# busadapt.net
KiCad netlist of a schematic drawn in EAGLE
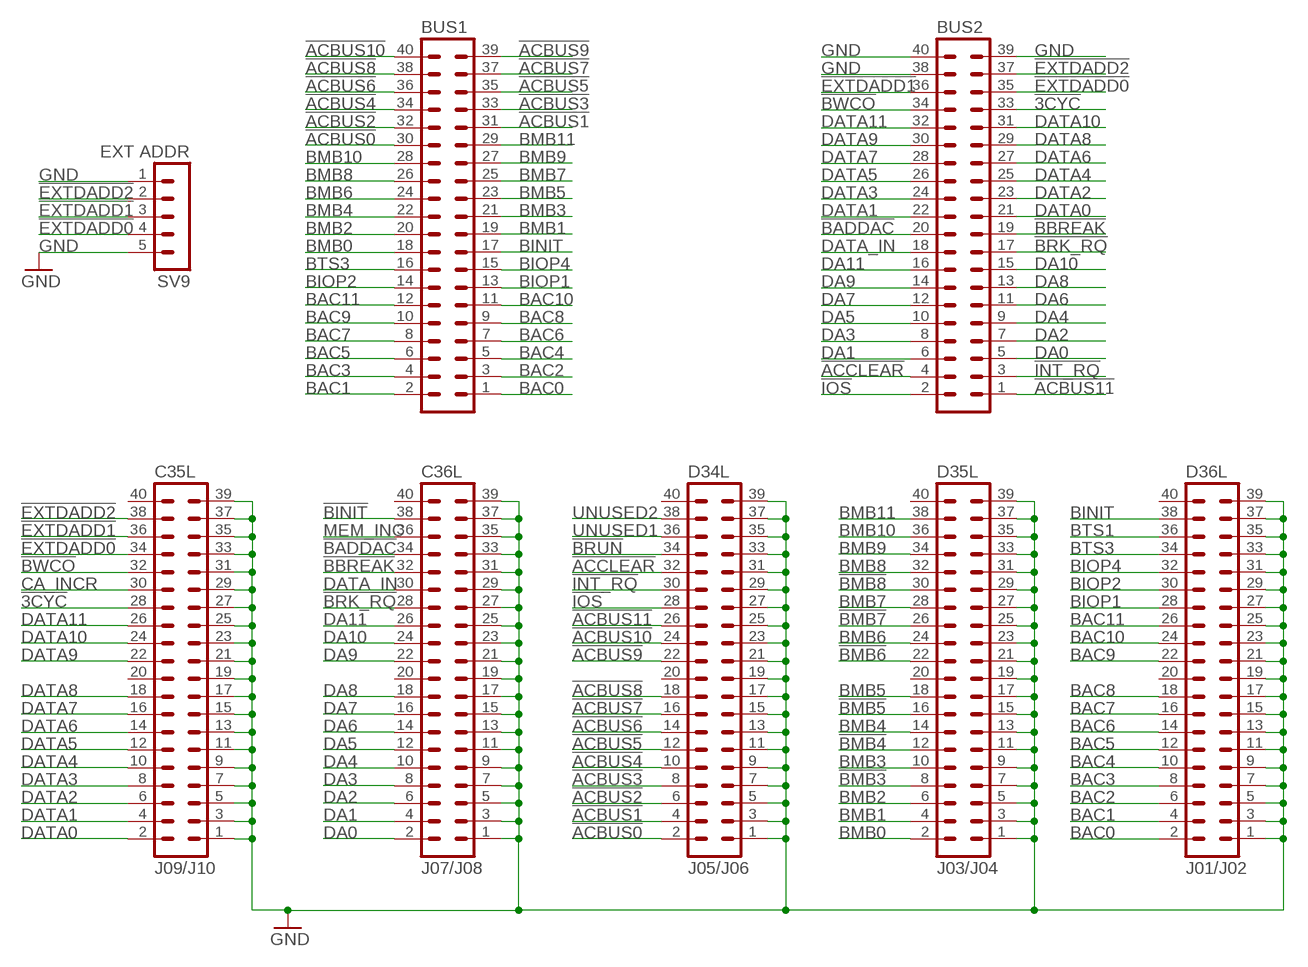
[diagram p0: schematic, sheet 1]

(export (version "E")
  (design (tool "Eeschema 10.0.6"))
  (components
    (comp (ref "BUS1")
      (value "MA20-2")
      (footprint "eagle-import:MA20-2")
      (libsource (lib "eagle-import") (part "MA20-2"))
    )
    (comp (ref "BUS2")
      (value "MA20-2")
      (footprint "eagle-import:MA20-2")
      (libsource (lib "eagle-import") (part "MA20-2"))
    )
    (comp (ref "C35L")
      (value "J09/J10")
      (footprint "eagle-import:MA20-2")
      (libsource (lib "eagle-import") (part "MA20-2"))
    )
    (comp (ref "C36L")
      (value "J07/J08")
      (footprint "eagle-import:MA20-2")
      (libsource (lib "eagle-import") (part "MA20-2"))
    )
    (comp (ref "D34L")
      (value "J05/J06")
      (footprint "eagle-import:MA20-2")
      (libsource (lib "eagle-import") (part "MA20-2"))
    )
    (comp (ref "D35L")
      (value "J03/J04")
      (footprint "eagle-import:MA20-2")
      (libsource (lib "eagle-import") (part "MA20-2"))
    )
    (comp (ref "D36L")
      (value "J01/J02")
      (footprint "eagle-import:MA20-2")
      (libsource (lib "eagle-import") (part "MA20-2"))
    )
    (comp (ref "SV9")
      (value "EXT ADDR")
      (footprint "eagle-import:MA05-1")
      (libsource (lib "eagle-import") (part "MA05-1"))
    )
  )
  (nets
    (net (code "1") (name "/BAC0") (class "Default")
      (node (ref "BUS1") (pin "1") (pinfunction "1_1") (pintype "passive"))
      (node (ref "D36L") (pin "2") (pinfunction "2_2") (pintype "passive"))
    )
    (net (code "2") (name "/BAC1") (class "Default")
      (node (ref "BUS1") (pin "2") (pinfunction "2_2") (pintype "passive"))
      (node (ref "D36L") (pin "4") (pinfunction "4_4") (pintype "passive"))
    )
    (net (code "3") (name "/BAC2") (class "Default")
      (node (ref "BUS1") (pin "3") (pinfunction "3_3") (pintype "passive"))
      (node (ref "D36L") (pin "6") (pinfunction "6_6") (pintype "passive"))
    )
    (net (code "4") (name "/BAC3") (class "Default")
      (node (ref "BUS1") (pin "4") (pinfunction "4_4") (pintype "passive"))
      (node (ref "D36L") (pin "8") (pinfunction "8_8") (pintype "passive"))
    )
    (net (code "5") (name "/BAC4") (class "Default")
      (node (ref "BUS1") (pin "5") (pinfunction "5_5") (pintype "passive"))
      (node (ref "D36L") (pin "10") (pinfunction "10_10") (pintype "passive"))
    )
    (net (code "6") (name "/BAC5") (class "Default")
      (node (ref "BUS1") (pin "6") (pinfunction "6_6") (pintype "passive"))
      (node (ref "D36L") (pin "12") (pinfunction "12_12") (pintype "passive"))
    )
    (net (code "7") (name "/BAC6") (class "Default")
      (node (ref "BUS1") (pin "7") (pinfunction "7_7") (pintype "passive"))
      (node (ref "D36L") (pin "14") (pinfunction "14_14") (pintype "passive"))
    )
    (net (code "8") (name "/BAC7") (class "Default")
      (node (ref "BUS1") (pin "8") (pinfunction "8_8") (pintype "passive"))
      (node (ref "D36L") (pin "16") (pinfunction "16_16") (pintype "passive"))
    )
    (net (code "9") (name "/BAC8") (class "Default")
      (node (ref "BUS1") (pin "9") (pinfunction "9_9") (pintype "passive"))
      (node (ref "D36L") (pin "18") (pinfunction "18_18") (pintype "passive"))
    )
    (net (code "10") (name "/BAC9") (class "Default")
      (node (ref "BUS1") (pin "10") (pinfunction "10_10") (pintype "passive"))
      (node (ref "D36L") (pin "22") (pinfunction "22_22") (pintype "passive"))
    )
    (net (code "11") (name "/BAC10") (class "Default")
      (node (ref "BUS1") (pin "11") (pinfunction "11_11") (pintype "passive"))
      (node (ref "D36L") (pin "24") (pinfunction "24_24") (pintype "passive"))
    )
    (net (code "12") (name "/BAC11") (class "Default")
      (node (ref "BUS1") (pin "12") (pinfunction "12_12") (pintype "passive"))
      (node (ref "D36L") (pin "26") (pinfunction "26_26") (pintype "passive"))
    )
    (net (code "13") (name "/BINIT") (class "Default")
      (node (ref "BUS1") (pin "17") (pinfunction "17_17") (pintype "passive"))
      (node (ref "D36L") (pin "38") (pinfunction "38_38") (pintype "passive"))
    )
    (net (code "14") (name "/BIOP1") (class "Default")
      (node (ref "BUS1") (pin "13") (pinfunction "13_13") (pintype "passive"))
      (node (ref "D36L") (pin "28") (pinfunction "28_28") (pintype "passive"))
    )
    (net (code "15") (name "/BIOP2") (class "Default")
      (node (ref "BUS1") (pin "14") (pinfunction "14_14") (pintype "passive"))
      (node (ref "D36L") (pin "30") (pinfunction "30_30") (pintype "passive"))
    )
    (net (code "16") (name "/BIOP4") (class "Default")
      (node (ref "BUS1") (pin "15") (pinfunction "15_15") (pintype "passive"))
      (node (ref "D36L") (pin "32") (pinfunction "32_32") (pintype "passive"))
    )
    (net (code "17") (name "/BMB0") (class "Default")
      (node (ref "BUS1") (pin "18") (pinfunction "18_18") (pintype "passive"))
      (node (ref "D35L") (pin "2") (pinfunction "2_2") (pintype "passive"))
    )
    (net (code "18") (name "/BMB1") (class "Default")
      (node (ref "BUS1") (pin "19") (pinfunction "19_19") (pintype "passive"))
      (node (ref "D35L") (pin "4") (pinfunction "4_4") (pintype "passive"))
    )
    (net (code "19") (name "/BMB2") (class "Default")
      (node (ref "BUS1") (pin "20") (pinfunction "20_20") (pintype "passive"))
      (node (ref "D35L") (pin "6") (pinfunction "6_6") (pintype "passive"))
    )
    (net (code "20") (name "/BMB3") (class "Default")
      (node (ref "BUS1") (pin "21") (pinfunction "21_21") (pintype "passive"))
      (node (ref "D35L") (pin "10") (pinfunction "10_10") (pintype "passive"))
    )
    (net (code "21") (name "/BMB4") (class "Default")
      (node (ref "BUS1") (pin "22") (pinfunction "22_22") (pintype "passive"))
      (node (ref "D35L") (pin "14") (pinfunction "14_14") (pintype "passive"))
    )
    (net (code "22") (name "/BMB5") (class "Default")
      (node (ref "BUS1") (pin "23") (pinfunction "23_23") (pintype "passive"))
      (node (ref "D35L") (pin "18") (pinfunction "18_18") (pintype "passive"))
    )
    (net (code "23") (name "/BMB6") (class "Default")
      (node (ref "BUS1") (pin "24") (pinfunction "24_24") (pintype "passive"))
      (node (ref "D35L") (pin "24") (pinfunction "24_24") (pintype "passive"))
    )
    (net (code "24") (name "/BMB7") (class "Default")
      (node (ref "BUS1") (pin "25") (pinfunction "25_25") (pintype "passive"))
      (node (ref "D35L") (pin "28") (pinfunction "28_28") (pintype "passive"))
    )
    (net (code "25") (name "/BMB8") (class "Default")
      (node (ref "BUS1") (pin "26") (pinfunction "26_26") (pintype "passive"))
      (node (ref "D35L") (pin "32") (pinfunction "32_32") (pintype "passive"))
    )
    (net (code "26") (name "/BMB9") (class "Default")
      (node (ref "BUS1") (pin "27") (pinfunction "27_27") (pintype "passive"))
      (node (ref "D35L") (pin "34") (pinfunction "34_34") (pintype "passive"))
    )
    (net (code "27") (name "/BMB10") (class "Default")
      (node (ref "BUS1") (pin "28") (pinfunction "28_28") (pintype "passive"))
      (node (ref "D35L") (pin "36") (pinfunction "36_36") (pintype "passive"))
    )
    (net (code "28") (name "/BMB11") (class "Default")
      (node (ref "BUS1") (pin "29") (pinfunction "29_29") (pintype "passive"))
      (node (ref "D35L") (pin "38") (pinfunction "38_38") (pintype "passive"))
    )
    (net (code "29") (name "/BTS1") (class "Default")
      (node (ref "D36L") (pin "36") (pinfunction "36_36") (pintype "passive"))
    )
    (net (code "30") (name "/BTS3") (class "Default")
      (node (ref "BUS1") (pin "16") (pinfunction "16_16") (pintype "passive"))
      (node (ref "D36L") (pin "34") (pinfunction "34_34") (pintype "passive"))
    )
    (net (code "31") (name "/CA_INCR") (class "Default")
      (node (ref "C35L") (pin "30") (pinfunction "30_30") (pintype "passive"))
    )
    (net (code "32") (name "/DA0") (class "Default")
      (node (ref "BUS2") (pin "5") (pinfunction "5_5") (pintype "passive"))
      (node (ref "C36L") (pin "2") (pinfunction "2_2") (pintype "passive"))
    )
    (net (code "33") (name "/DA1") (class "Default")
      (node (ref "BUS2") (pin "6") (pinfunction "6_6") (pintype "passive"))
      (node (ref "C36L") (pin "4") (pinfunction "4_4") (pintype "passive"))
    )
    (net (code "34") (name "/DA2") (class "Default")
      (node (ref "BUS2") (pin "7") (pinfunction "7_7") (pintype "passive"))
      (node (ref "C36L") (pin "6") (pinfunction "6_6") (pintype "passive"))
    )
    (net (code "35") (name "/DA3") (class "Default")
      (node (ref "BUS2") (pin "8") (pinfunction "8_8") (pintype "passive"))
      (node (ref "C36L") (pin "8") (pinfunction "8_8") (pintype "passive"))
    )
    (net (code "36") (name "/DA4") (class "Default")
      (node (ref "BUS2") (pin "9") (pinfunction "9_9") (pintype "passive"))
      (node (ref "C36L") (pin "10") (pinfunction "10_10") (pintype "passive"))
    )
    (net (code "37") (name "/DA5") (class "Default")
      (node (ref "BUS2") (pin "10") (pinfunction "10_10") (pintype "passive"))
      (node (ref "C36L") (pin "12") (pinfunction "12_12") (pintype "passive"))
    )
    (net (code "38") (name "/DA6") (class "Default")
      (node (ref "BUS2") (pin "11") (pinfunction "11_11") (pintype "passive"))
      (node (ref "C36L") (pin "14") (pinfunction "14_14") (pintype "passive"))
    )
    (net (code "39") (name "/DA7") (class "Default")
      (node (ref "BUS2") (pin "12") (pinfunction "12_12") (pintype "passive"))
      (node (ref "C36L") (pin "16") (pinfunction "16_16") (pintype "passive"))
    )
    (net (code "40") (name "/DA8") (class "Default")
      (node (ref "BUS2") (pin "13") (pinfunction "13_13") (pintype "passive"))
      (node (ref "C36L") (pin "18") (pinfunction "18_18") (pintype "passive"))
    )
    (net (code "41") (name "/DA9") (class "Default")
      (node (ref "BUS2") (pin "14") (pinfunction "14_14") (pintype "passive"))
      (node (ref "C36L") (pin "22") (pinfunction "22_22") (pintype "passive"))
    )
    (net (code "42") (name "/DA10") (class "Default")
      (node (ref "BUS2") (pin "15") (pinfunction "15_15") (pintype "passive"))
      (node (ref "C36L") (pin "24") (pinfunction "24_24") (pintype "passive"))
    )
    (net (code "43") (name "/DA11") (class "Default")
      (node (ref "BUS2") (pin "16") (pinfunction "16_16") (pintype "passive"))
      (node (ref "C36L") (pin "26") (pinfunction "26_26") (pintype "passive"))
    )
    (net (code "44") (name "/DATA0") (class "Default")
      (node (ref "BUS2") (pin "21") (pinfunction "21_21") (pintype "passive"))
      (node (ref "C35L") (pin "2") (pinfunction "2_2") (pintype "passive"))
    )
    (net (code "45") (name "/DATA1") (class "Default")
      (node (ref "BUS2") (pin "22") (pinfunction "22_22") (pintype "passive"))
      (node (ref "C35L") (pin "4") (pinfunction "4_4") (pintype "passive"))
    )
    (net (code "46") (name "/DATA2") (class "Default")
      (node (ref "BUS2") (pin "23") (pinfunction "23_23") (pintype "passive"))
      (node (ref "C35L") (pin "6") (pinfunction "6_6") (pintype "passive"))
    )
    (net (code "47") (name "/DATA3") (class "Default")
      (node (ref "BUS2") (pin "24") (pinfunction "24_24") (pintype "passive"))
      (node (ref "C35L") (pin "8") (pinfunction "8_8") (pintype "passive"))
    )
    (net (code "48") (name "/DATA4") (class "Default")
      (node (ref "BUS2") (pin "25") (pinfunction "25_25") (pintype "passive"))
      (node (ref "C35L") (pin "10") (pinfunction "10_10") (pintype "passive"))
    )
    (net (code "49") (name "/DATA5") (class "Default")
      (node (ref "BUS2") (pin "26") (pinfunction "26_26") (pintype "passive"))
      (node (ref "C35L") (pin "12") (pinfunction "12_12") (pintype "passive"))
    )
    (net (code "50") (name "/DATA6") (class "Default")
      (node (ref "BUS2") (pin "27") (pinfunction "27_27") (pintype "passive"))
      (node (ref "C35L") (pin "14") (pinfunction "14_14") (pintype "passive"))
    )
    (net (code "51") (name "/DATA7") (class "Default")
      (node (ref "BUS2") (pin "28") (pinfunction "28_28") (pintype "passive"))
      (node (ref "C35L") (pin "16") (pinfunction "16_16") (pintype "passive"))
    )
    (net (code "52") (name "/DATA8") (class "Default")
      (node (ref "BUS2") (pin "29") (pinfunction "29_29") (pintype "passive"))
      (node (ref "C35L") (pin "18") (pinfunction "18_18") (pintype "passive"))
    )
    (net (code "53") (name "/DATA9") (class "Default")
      (node (ref "BUS2") (pin "30") (pinfunction "30_30") (pintype "passive"))
      (node (ref "C35L") (pin "22") (pinfunction "22_22") (pintype "passive"))
    )
    (net (code "54") (name "/DATA10") (class "Default")
      (node (ref "BUS2") (pin "31") (pinfunction "31_31") (pintype "passive"))
      (node (ref "C35L") (pin "24") (pinfunction "24_24") (pintype "passive"))
    )
    (net (code "55") (name "/DATA11") (class "Default")
      (node (ref "BUS2") (pin "32") (pinfunction "32_32") (pintype "passive"))
      (node (ref "C35L") (pin "26") (pinfunction "26_26") (pintype "passive"))
    )
    (net (code "56") (name "/DATA_IN") (class "Default")
      (node (ref "BUS2") (pin "18") (pinfunction "18_18") (pintype "passive"))
      (node (ref "C36L") (pin "30") (pinfunction "30_30") (pintype "passive"))
    )
    (net (code "57") (name "/MEM_INC") (class "Default")
      (node (ref "C36L") (pin "36") (pinfunction "36_36") (pintype "passive"))
    )
    (net (code "58") (name "/UNUSED1") (class "Default")
      (node (ref "D34L") (pin "36") (pinfunction "36_36") (pintype "passive"))
    )
    (net (code "59") (name "/UNUSED2") (class "Default")
      (node (ref "D34L") (pin "38") (pinfunction "38_38") (pintype "passive"))
    )
    (net (code "60") (name "/~{3CYC}") (class "Default")
      (node (ref "BUS2") (pin "33") (pinfunction "33_33") (pintype "passive"))
      (node (ref "C35L") (pin "28") (pinfunction "28_28") (pintype "passive"))
    )
    (net (code "61") (name "/~{ACBUS0}") (class "Default")
      (node (ref "BUS1") (pin "30") (pinfunction "30_30") (pintype "passive"))
      (node (ref "D34L") (pin "2") (pinfunction "2_2") (pintype "passive"))
    )
    (net (code "62") (name "/~{ACBUS1}") (class "Default")
      (node (ref "BUS1") (pin "31") (pinfunction "31_31") (pintype "passive"))
      (node (ref "D34L") (pin "4") (pinfunction "4_4") (pintype "passive"))
    )
    (net (code "63") (name "/~{ACBUS2}") (class "Default")
      (node (ref "BUS1") (pin "32") (pinfunction "32_32") (pintype "passive"))
      (node (ref "D34L") (pin "6") (pinfunction "6_6") (pintype "passive"))
    )
    (net (code "64") (name "/~{ACBUS3}") (class "Default")
      (node (ref "BUS1") (pin "33") (pinfunction "33_33") (pintype "passive"))
      (node (ref "D34L") (pin "8") (pinfunction "8_8") (pintype "passive"))
    )
    (net (code "65") (name "/~{ACBUS4}") (class "Default")
      (node (ref "BUS1") (pin "34") (pinfunction "34_34") (pintype "passive"))
      (node (ref "D34L") (pin "10") (pinfunction "10_10") (pintype "passive"))
    )
    (net (code "66") (name "/~{ACBUS5}") (class "Default")
      (node (ref "BUS1") (pin "35") (pinfunction "35_35") (pintype "passive"))
      (node (ref "D34L") (pin "12") (pinfunction "12_12") (pintype "passive"))
    )
    (net (code "67") (name "/~{ACBUS6}") (class "Default")
      (node (ref "BUS1") (pin "36") (pinfunction "36_36") (pintype "passive"))
      (node (ref "D34L") (pin "14") (pinfunction "14_14") (pintype "passive"))
    )
    (net (code "68") (name "/~{ACBUS7}") (class "Default")
      (node (ref "BUS1") (pin "37") (pinfunction "37_37") (pintype "passive"))
      (node (ref "D34L") (pin "16") (pinfunction "16_16") (pintype "passive"))
    )
    (net (code "69") (name "/~{ACBUS8}") (class "Default")
      (node (ref "BUS1") (pin "38") (pinfunction "38_38") (pintype "passive"))
      (node (ref "D34L") (pin "18") (pinfunction "18_18") (pintype "passive"))
    )
    (net (code "70") (name "/~{ACBUS9}") (class "Default")
      (node (ref "BUS1") (pin "39") (pinfunction "39_39") (pintype "passive"))
      (node (ref "D34L") (pin "22") (pinfunction "22_22") (pintype "passive"))
    )
    (net (code "71") (name "/~{ACBUS10}") (class "Default")
      (node (ref "BUS1") (pin "40") (pinfunction "40_40") (pintype "passive"))
      (node (ref "D34L") (pin "24") (pinfunction "24_24") (pintype "passive"))
    )
    (net (code "72") (name "/~{ACBUS11}") (class "Default")
      (node (ref "BUS2") (pin "1") (pinfunction "1_1") (pintype "passive"))
      (node (ref "D34L") (pin "26") (pinfunction "26_26") (pintype "passive"))
    )
    (net (code "73") (name "/~{ACCLEAR}") (class "Default")
      (node (ref "BUS2") (pin "4") (pinfunction "4_4") (pintype "passive"))
      (node (ref "D34L") (pin "32") (pinfunction "32_32") (pintype "passive"))
    )
    (net (code "74") (name "/~{BADDAC}") (class "Default")
      (node (ref "BUS2") (pin "20") (pinfunction "20_20") (pintype "passive"))
      (node (ref "C36L") (pin "34") (pinfunction "34_34") (pintype "passive"))
    )
    (net (code "75") (name "/~{BBREAK}") (class "Default")
      (node (ref "BUS2") (pin "19") (pinfunction "19_19") (pintype "passive"))
      (node (ref "C36L") (pin "32") (pinfunction "32_32") (pintype "passive"))
    )
    (net (code "76") (name "/~{BINIT}") (class "Default")
      (node (ref "C36L") (pin "38") (pinfunction "38_38") (pintype "passive"))
    )
    (net (code "77") (name "/~{BMB3}") (class "Default")
      (node (ref "D35L") (pin "8") (pinfunction "8_8") (pintype "passive"))
    )
    (net (code "78") (name "/~{BMB4}") (class "Default")
      (node (ref "D35L") (pin "12") (pinfunction "12_12") (pintype "passive"))
    )
    (net (code "79") (name "/~{BMB5}") (class "Default")
      (node (ref "D35L") (pin "16") (pinfunction "16_16") (pintype "passive"))
    )
    (net (code "80") (name "/~{BMB6}") (class "Default")
      (node (ref "D35L") (pin "22") (pinfunction "22_22") (pintype "passive"))
    )
    (net (code "81") (name "/~{BMB7}") (class "Default")
      (node (ref "D35L") (pin "26") (pinfunction "26_26") (pintype "passive"))
    )
    (net (code "82") (name "/~{BMB8}") (class "Default")
      (node (ref "D35L") (pin "30") (pinfunction "30_30") (pintype "passive"))
    )
    (net (code "83") (name "/~{BRK_RQ}") (class "Default")
      (node (ref "BUS2") (pin "17") (pinfunction "17_17") (pintype "passive"))
      (node (ref "C36L") (pin "28") (pinfunction "28_28") (pintype "passive"))
    )
    (net (code "84") (name "/~{BRUN}") (class "Default")
      (node (ref "D34L") (pin "34") (pinfunction "34_34") (pintype "passive"))
    )
    (net (code "85") (name "/~{BWCO}") (class "Default")
      (node (ref "BUS2") (pin "34") (pinfunction "34_34") (pintype "passive"))
      (node (ref "C35L") (pin "32") (pinfunction "32_32") (pintype "passive"))
    )
    (net (code "86") (name "/~{EXTDADD0}") (class "Default")
      (node (ref "BUS2") (pin "35") (pinfunction "35_35") (pintype "passive"))
      (node (ref "C35L") (pin "34") (pinfunction "34_34") (pintype "passive"))
      (node (ref "SV9") (pin "4") (pinfunction "4_4") (pintype "passive"))
    )
    (net (code "87") (name "/~{EXTDADD1}") (class "Default")
      (node (ref "BUS2") (pin "36") (pinfunction "36_36") (pintype "passive"))
      (node (ref "C35L") (pin "36") (pinfunction "36_36") (pintype "passive"))
      (node (ref "SV9") (pin "3") (pinfunction "3_3") (pintype "passive"))
    )
    (net (code "88") (name "/~{EXTDADD2}") (class "Default")
      (node (ref "BUS2") (pin "37") (pinfunction "37_37") (pintype "passive"))
      (node (ref "C35L") (pin "38") (pinfunction "38_38") (pintype "passive"))
      (node (ref "SV9") (pin "2") (pinfunction "2_2") (pintype "passive"))
    )
    (net (code "89") (name "/~{INT_RQ}") (class "Default")
      (node (ref "BUS2") (pin "3") (pinfunction "3_3") (pintype "passive"))
      (node (ref "D34L") (pin "30") (pinfunction "30_30") (pintype "passive"))
    )
    (net (code "90") (name "/~{IOS}") (class "Default")
      (node (ref "BUS2") (pin "2") (pinfunction "2_2") (pintype "passive"))
      (node (ref "D34L") (pin "28") (pinfunction "28_28") (pintype "passive"))
    )
    (net (code "91") (name "GND") (class "Default")
      (node (ref "BUS2") (pin "38") (pinfunction "38_38") (pintype "passive"))
      (node (ref "BUS2") (pin "39") (pinfunction "39_39") (pintype "passive"))
      (node (ref "BUS2") (pin "40") (pinfunction "40_40") (pintype "passive"))
      (node (ref "C35L") (pin "1") (pinfunction "1_1") (pintype "passive"))
      (node (ref "C35L") (pin "11") (pinfunction "11_11") (pintype "passive"))
      (node (ref "C35L") (pin "13") (pinfunction "13_13") (pintype "passive"))
      (node (ref "C35L") (pin "15") (pinfunction "15_15") (pintype "passive"))
      (node (ref "C35L") (pin "17") (pinfunction "17_17") (pintype "passive"))
      (node (ref "C35L") (pin "19") (pinfunction "19_19") (pintype "passive"))
      (node (ref "C35L") (pin "21") (pinfunction "21_21") (pintype "passive"))
      (node (ref "C35L") (pin "23") (pinfunction "23_23") (pintype "passive"))
      (node (ref "C35L") (pin "25") (pinfunction "25_25") (pintype "passive"))
      (node (ref "C35L") (pin "27") (pinfunction "27_27") (pintype "passive"))
      (node (ref "C35L") (pin "29") (pinfunction "29_29") (pintype "passive"))
      (node (ref "C35L") (pin "3") (pinfunction "3_3") (pintype "passive"))
      (node (ref "C35L") (pin "31") (pinfunction "31_31") (pintype "passive"))
      (node (ref "C35L") (pin "33") (pinfunction "33_33") (pintype "passive"))
      (node (ref "C35L") (pin "35") (pinfunction "35_35") (pintype "passive"))
      (node (ref "C35L") (pin "37") (pinfunction "37_37") (pintype "passive"))
      (node (ref "C35L") (pin "39") (pinfunction "39_39") (pintype "passive"))
      (node (ref "C35L") (pin "5") (pinfunction "5_5") (pintype "passive"))
      (node (ref "C35L") (pin "7") (pinfunction "7_7") (pintype "passive"))
      (node (ref "C35L") (pin "9") (pinfunction "9_9") (pintype "passive"))
      (node (ref "C36L") (pin "1") (pinfunction "1_1") (pintype "passive"))
      (node (ref "C36L") (pin "11") (pinfunction "11_11") (pintype "passive"))
      (node (ref "C36L") (pin "13") (pinfunction "13_13") (pintype "passive"))
      (node (ref "C36L") (pin "15") (pinfunction "15_15") (pintype "passive"))
      (node (ref "C36L") (pin "17") (pinfunction "17_17") (pintype "passive"))
      (node (ref "C36L") (pin "19") (pinfunction "19_19") (pintype "passive"))
      (node (ref "C36L") (pin "21") (pinfunction "21_21") (pintype "passive"))
      (node (ref "C36L") (pin "23") (pinfunction "23_23") (pintype "passive"))
      (node (ref "C36L") (pin "25") (pinfunction "25_25") (pintype "passive"))
      (node (ref "C36L") (pin "27") (pinfunction "27_27") (pintype "passive"))
      (node (ref "C36L") (pin "29") (pinfunction "29_29") (pintype "passive"))
      (node (ref "C36L") (pin "3") (pinfunction "3_3") (pintype "passive"))
      (node (ref "C36L") (pin "31") (pinfunction "31_31") (pintype "passive"))
      (node (ref "C36L") (pin "33") (pinfunction "33_33") (pintype "passive"))
      (node (ref "C36L") (pin "35") (pinfunction "35_35") (pintype "passive"))
      (node (ref "C36L") (pin "37") (pinfunction "37_37") (pintype "passive"))
      (node (ref "C36L") (pin "39") (pinfunction "39_39") (pintype "passive"))
      (node (ref "C36L") (pin "5") (pinfunction "5_5") (pintype "passive"))
      (node (ref "C36L") (pin "7") (pinfunction "7_7") (pintype "passive"))
      (node (ref "C36L") (pin "9") (pinfunction "9_9") (pintype "passive"))
      (node (ref "D34L") (pin "1") (pinfunction "1_1") (pintype "passive"))
      (node (ref "D34L") (pin "11") (pinfunction "11_11") (pintype "passive"))
      (node (ref "D34L") (pin "13") (pinfunction "13_13") (pintype "passive"))
      (node (ref "D34L") (pin "15") (pinfunction "15_15") (pintype "passive"))
      (node (ref "D34L") (pin "17") (pinfunction "17_17") (pintype "passive"))
      (node (ref "D34L") (pin "19") (pinfunction "19_19") (pintype "passive"))
      (node (ref "D34L") (pin "21") (pinfunction "21_21") (pintype "passive"))
      (node (ref "D34L") (pin "23") (pinfunction "23_23") (pintype "passive"))
      (node (ref "D34L") (pin "25") (pinfunction "25_25") (pintype "passive"))
      (node (ref "D34L") (pin "27") (pinfunction "27_27") (pintype "passive"))
      (node (ref "D34L") (pin "29") (pinfunction "29_29") (pintype "passive"))
      (node (ref "D34L") (pin "3") (pinfunction "3_3") (pintype "passive"))
      (node (ref "D34L") (pin "31") (pinfunction "31_31") (pintype "passive"))
      (node (ref "D34L") (pin "33") (pinfunction "33_33") (pintype "passive"))
      (node (ref "D34L") (pin "35") (pinfunction "35_35") (pintype "passive"))
      (node (ref "D34L") (pin "37") (pinfunction "37_37") (pintype "passive"))
      (node (ref "D34L") (pin "39") (pinfunction "39_39") (pintype "passive"))
      (node (ref "D34L") (pin "5") (pinfunction "5_5") (pintype "passive"))
      (node (ref "D34L") (pin "7") (pinfunction "7_7") (pintype "passive"))
      (node (ref "D34L") (pin "9") (pinfunction "9_9") (pintype "passive"))
      (node (ref "D35L") (pin "1") (pinfunction "1_1") (pintype "passive"))
      (node (ref "D35L") (pin "11") (pinfunction "11_11") (pintype "passive"))
      (node (ref "D35L") (pin "13") (pinfunction "13_13") (pintype "passive"))
      (node (ref "D35L") (pin "15") (pinfunction "15_15") (pintype "passive"))
      (node (ref "D35L") (pin "17") (pinfunction "17_17") (pintype "passive"))
      (node (ref "D35L") (pin "19") (pinfunction "19_19") (pintype "passive"))
      (node (ref "D35L") (pin "21") (pinfunction "21_21") (pintype "passive"))
      (node (ref "D35L") (pin "23") (pinfunction "23_23") (pintype "passive"))
      (node (ref "D35L") (pin "25") (pinfunction "25_25") (pintype "passive"))
      (node (ref "D35L") (pin "27") (pinfunction "27_27") (pintype "passive"))
      (node (ref "D35L") (pin "29") (pinfunction "29_29") (pintype "passive"))
      (node (ref "D35L") (pin "3") (pinfunction "3_3") (pintype "passive"))
      (node (ref "D35L") (pin "31") (pinfunction "31_31") (pintype "passive"))
      (node (ref "D35L") (pin "33") (pinfunction "33_33") (pintype "passive"))
      (node (ref "D35L") (pin "35") (pinfunction "35_35") (pintype "passive"))
      (node (ref "D35L") (pin "37") (pinfunction "37_37") (pintype "passive"))
      (node (ref "D35L") (pin "39") (pinfunction "39_39") (pintype "passive"))
      (node (ref "D35L") (pin "5") (pinfunction "5_5") (pintype "passive"))
      (node (ref "D35L") (pin "7") (pinfunction "7_7") (pintype "passive"))
      (node (ref "D35L") (pin "9") (pinfunction "9_9") (pintype "passive"))
      (node (ref "D36L") (pin "1") (pinfunction "1_1") (pintype "passive"))
      (node (ref "D36L") (pin "11") (pinfunction "11_11") (pintype "passive"))
      (node (ref "D36L") (pin "13") (pinfunction "13_13") (pintype "passive"))
      (node (ref "D36L") (pin "15") (pinfunction "15_15") (pintype "passive"))
      (node (ref "D36L") (pin "17") (pinfunction "17_17") (pintype "passive"))
      (node (ref "D36L") (pin "19") (pinfunction "19_19") (pintype "passive"))
      (node (ref "D36L") (pin "21") (pinfunction "21_21") (pintype "passive"))
      (node (ref "D36L") (pin "23") (pinfunction "23_23") (pintype "passive"))
      (node (ref "D36L") (pin "25") (pinfunction "25_25") (pintype "passive"))
      (node (ref "D36L") (pin "27") (pinfunction "27_27") (pintype "passive"))
      (node (ref "D36L") (pin "29") (pinfunction "29_29") (pintype "passive"))
      (node (ref "D36L") (pin "3") (pinfunction "3_3") (pintype "passive"))
      (node (ref "D36L") (pin "31") (pinfunction "31_31") (pintype "passive"))
      (node (ref "D36L") (pin "33") (pinfunction "33_33") (pintype "passive"))
      (node (ref "D36L") (pin "35") (pinfunction "35_35") (pintype "passive"))
      (node (ref "D36L") (pin "37") (pinfunction "37_37") (pintype "passive"))
      (node (ref "D36L") (pin "39") (pinfunction "39_39") (pintype "passive"))
      (node (ref "D36L") (pin "5") (pinfunction "5_5") (pintype "passive"))
      (node (ref "D36L") (pin "7") (pinfunction "7_7") (pintype "passive"))
      (node (ref "D36L") (pin "9") (pinfunction "9_9") (pintype "passive"))
      (node (ref "SV9") (pin "1") (pinfunction "1_1") (pintype "passive"))
      (node (ref "SV9") (pin "5") (pinfunction "5_5") (pintype "passive"))
    )
    (net (code "92") (name "unconnected-(C35L-Pad20)") (class "Default")
      (node (ref "C35L") (pin "20") (pinfunction "20_20") (pintype "passive"))
    )
    (net (code "93") (name "unconnected-(C35L-Pad40)") (class "Default")
      (node (ref "C35L") (pin "40") (pinfunction "40_40") (pintype "passive"))
    )
    (net (code "94") (name "unconnected-(C36L-Pad20)") (class "Default")
      (node (ref "C36L") (pin "20") (pinfunction "20_20") (pintype "passive"))
    )
    (net (code "95") (name "unconnected-(C36L-Pad40)") (class "Default")
      (node (ref "C36L") (pin "40") (pinfunction "40_40") (pintype "passive"))
    )
    (net (code "96") (name "unconnected-(D34L-Pad20)") (class "Default")
      (node (ref "D34L") (pin "20") (pinfunction "20_20") (pintype "passive"))
    )
    (net (code "97") (name "unconnected-(D34L-Pad40)") (class "Default")
      (node (ref "D34L") (pin "40") (pinfunction "40_40") (pintype "passive"))
    )
    (net (code "98") (name "unconnected-(D35L-Pad20)") (class "Default")
      (node (ref "D35L") (pin "20") (pinfunction "20_20") (pintype "passive"))
    )
    (net (code "99") (name "unconnected-(D35L-Pad40)") (class "Default")
      (node (ref "D35L") (pin "40") (pinfunction "40_40") (pintype "passive"))
    )
    (net (code "100") (name "unconnected-(D36L-Pad20)") (class "Default")
      (node (ref "D36L") (pin "20") (pinfunction "20_20") (pintype "passive"))
    )
    (net (code "101") (name "unconnected-(D36L-Pad40)") (class "Default")
      (node (ref "D36L") (pin "40") (pinfunction "40_40") (pintype "passive"))
    )
  )
)
